# USB_JTAG.net
KiCad netlist of a schematic drawn in Altium Designer
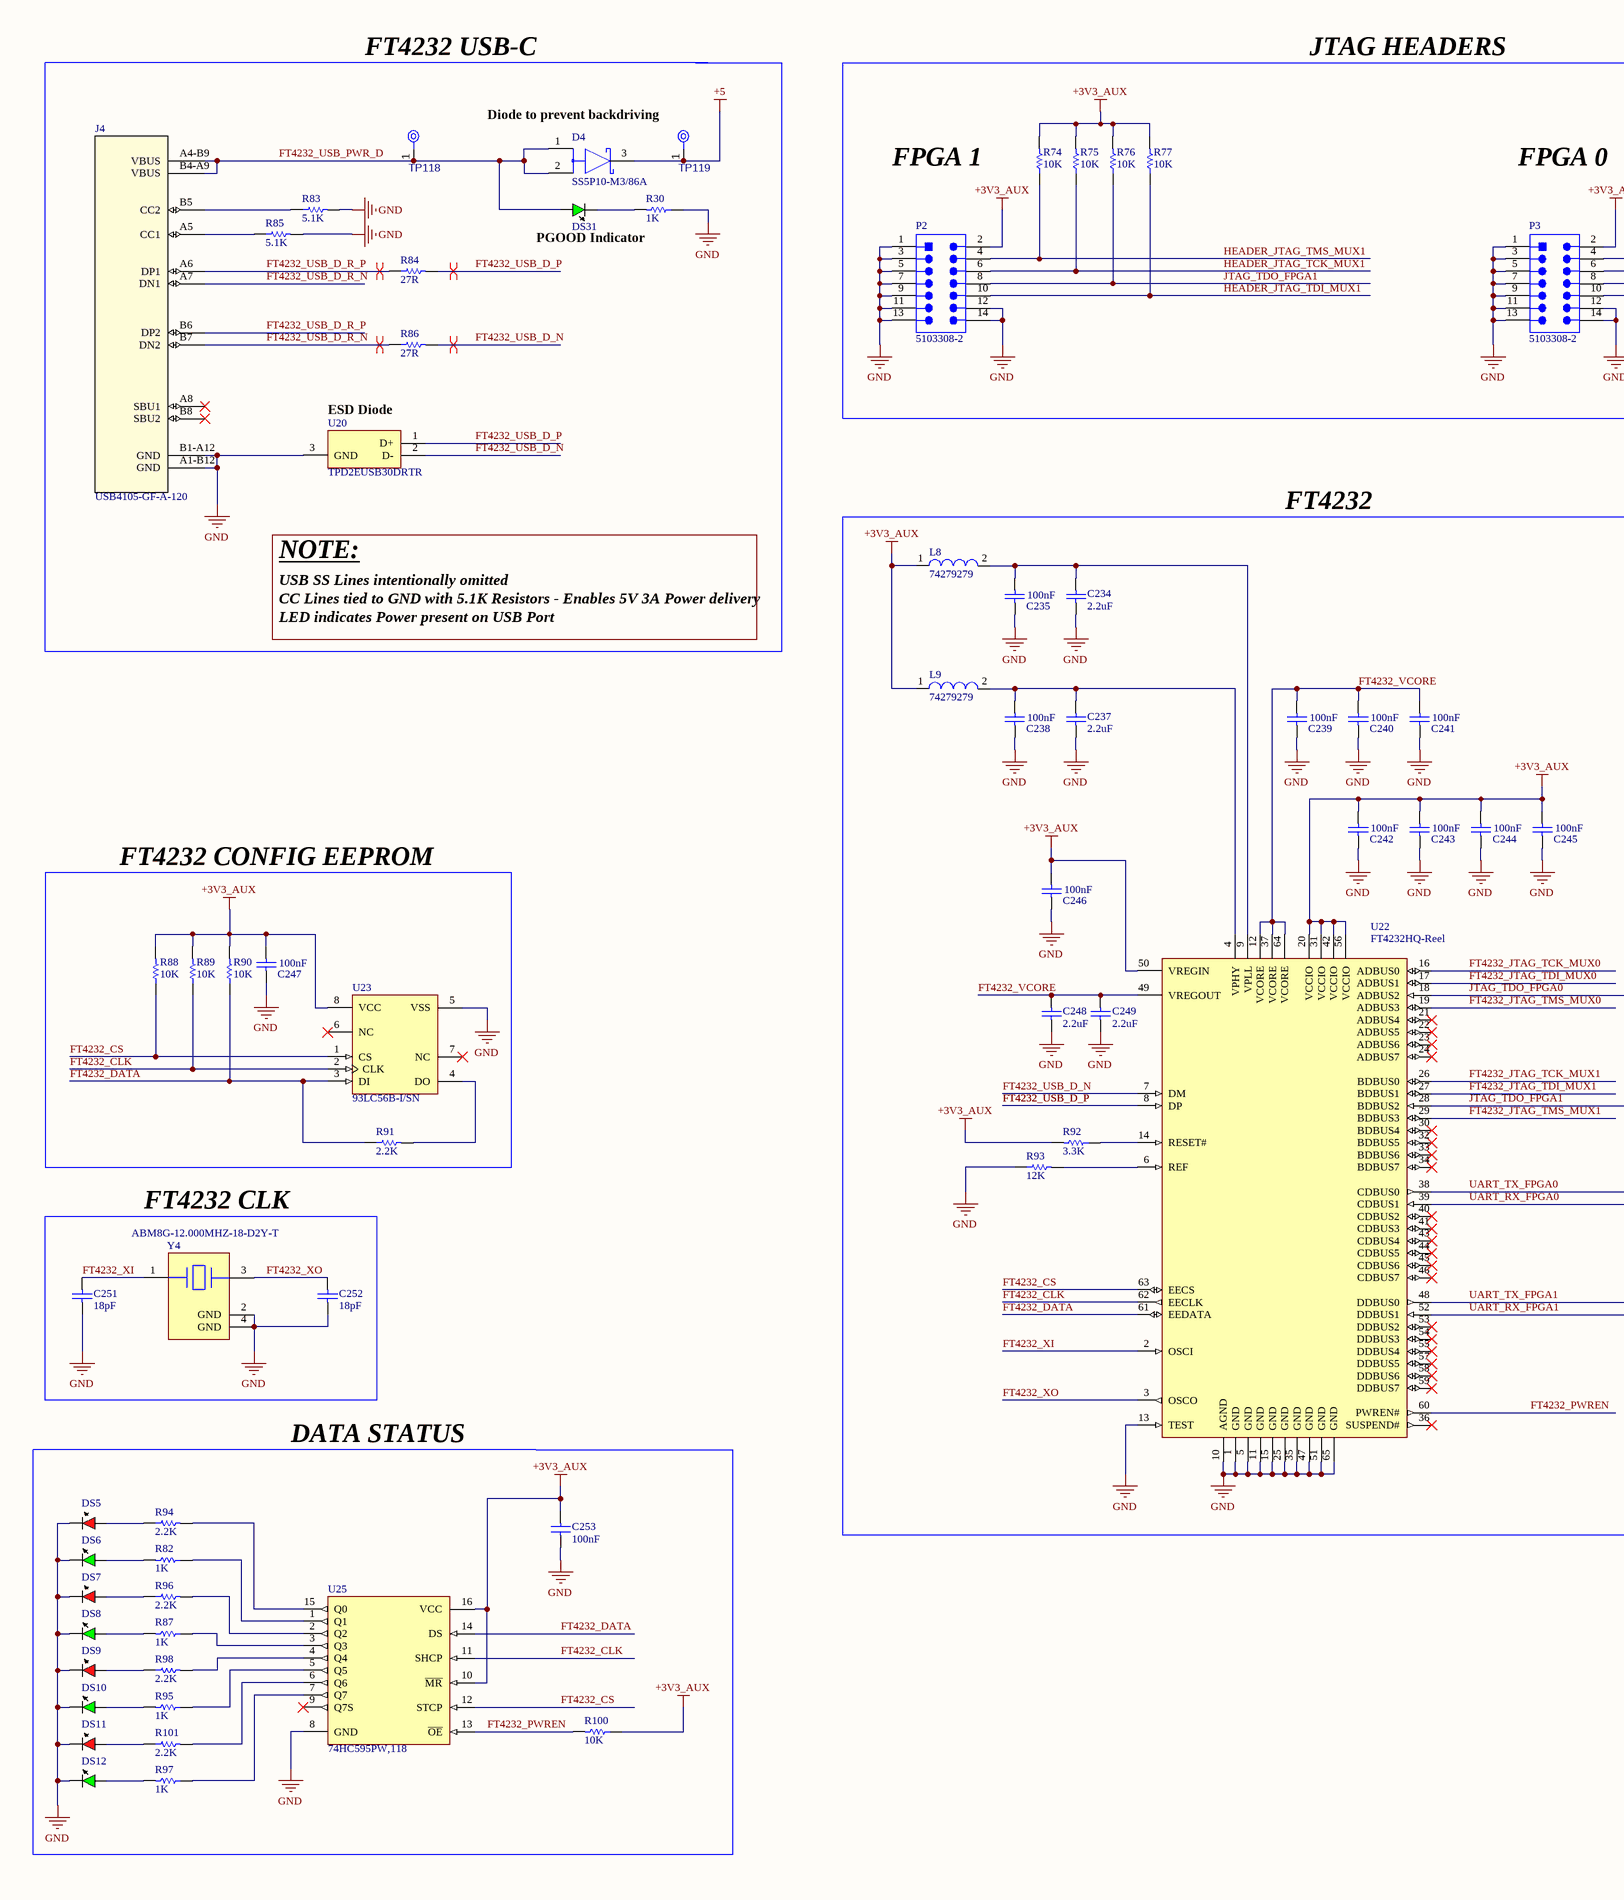
[diagram p0: USB JTAG.SchDoc, left]
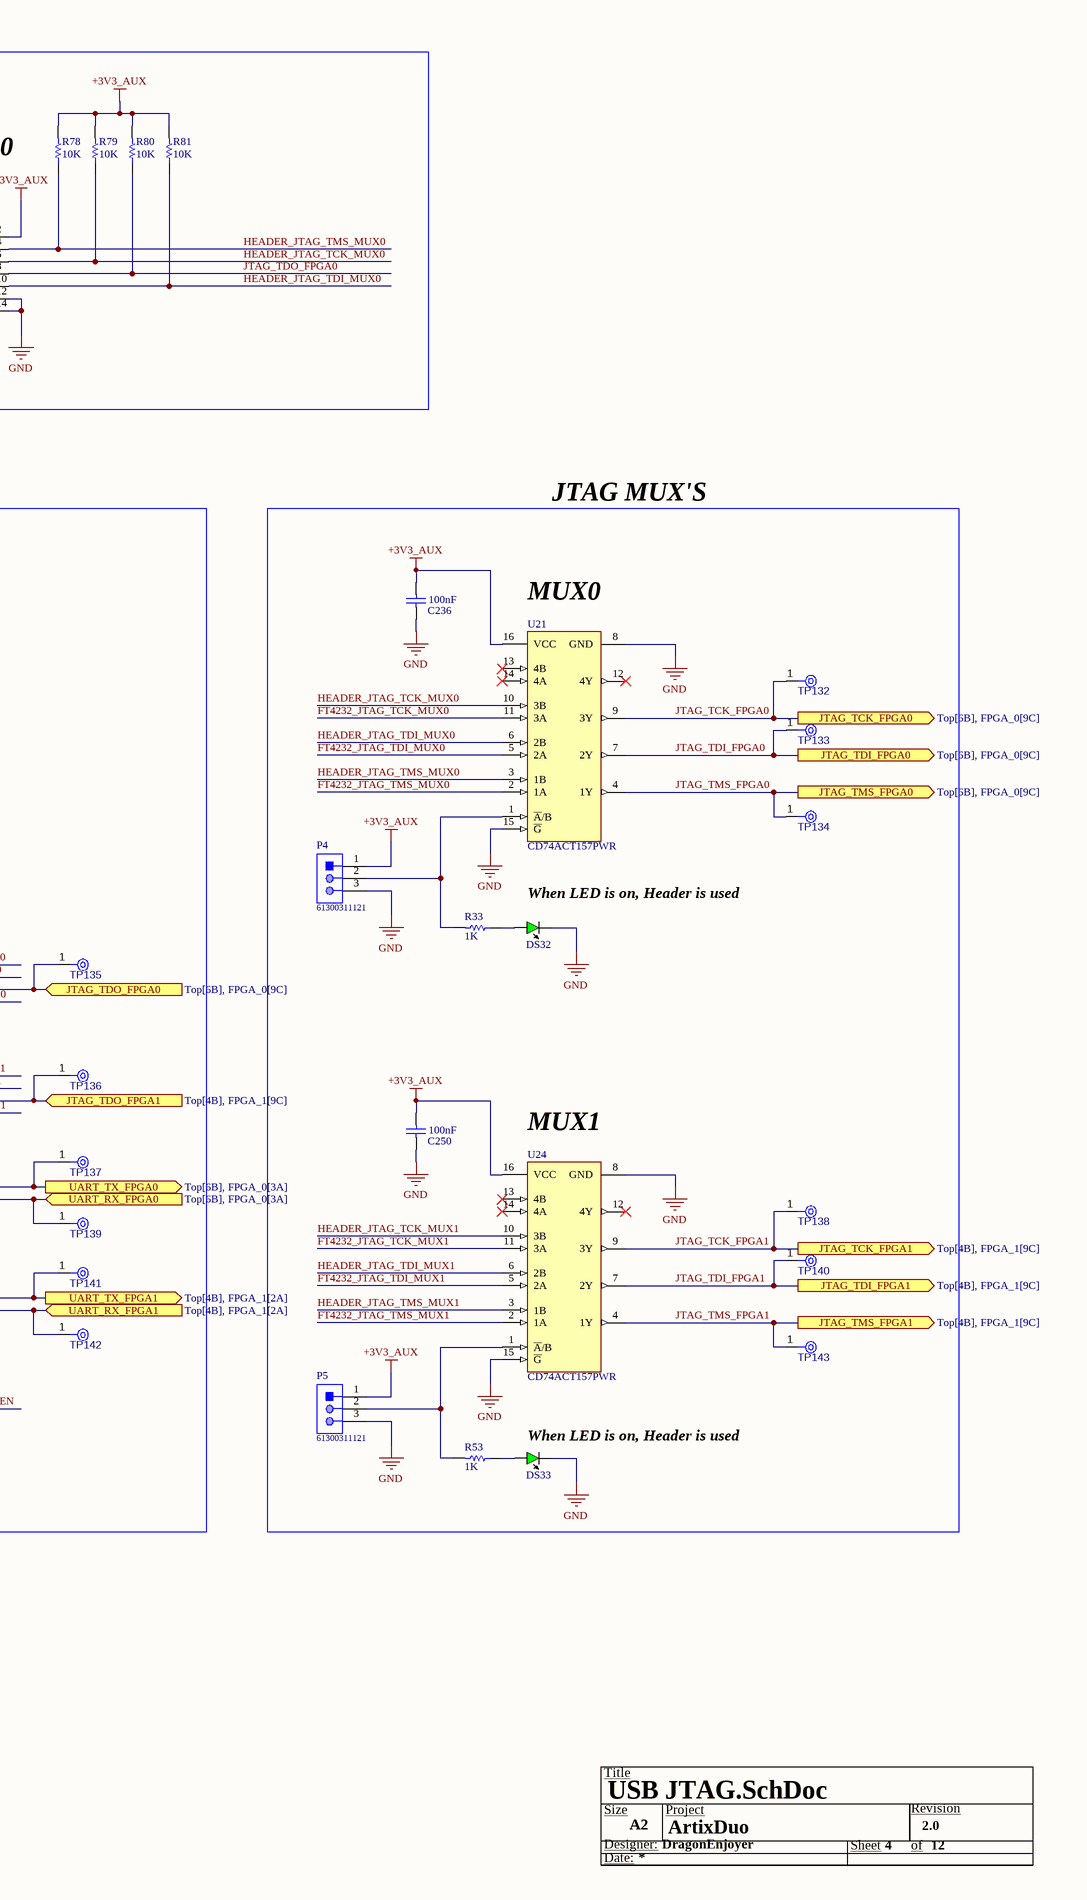
[diagram p1: USB JTAG.SchDoc, right]

(export (version "E")
  (design (tool "Eeschema 10.0.6"))
  (components
    (comp (ref "C234")
      (value "2.2uF")
      (footprint "CAPC1005X55X25NL05T10")
      (description "GRM155R60J225ME15D")
      (fields (field (name "MANUFACTURER") "Murata"))
      (libsource (lib "Altium Content Vault") (part "CAP"))
    )
    (comp (ref "C235")
      (value "100nF")
      (footprint "CAPC1005X05N")
      (description "Cap Ceramic 0.1uF 50V X7R 20% SMD 0402 125°C Paper T/R GRM155R71H104ME14J")
      (fields (field (name "VOLTAGE") "50V"))
      (libsource (lib "Main Workspace") (part "CAP"))
    )
    (comp (ref "C236")
      (value "100nF")
      (footprint "CAPC1005X05N")
      (description "Cap Ceramic 0.1uF 50V X7R 20% SMD 0402 125°C Paper T/R GRM155R71H104ME14J")
      (fields (field (name "VOLTAGE") "50V"))
      (libsource (lib "Main Workspace") (part "CAP"))
    )
    (comp (ref "C237")
      (value "2.2uF")
      (footprint "CAPC1005X55X25NL05T10")
      (description "GRM155R60J225ME15D")
      (fields (field (name "MANUFACTURER") "Murata"))
      (libsource (lib "Altium Content Vault") (part "CAP"))
    )
    (comp (ref "C238")
      (value "100nF")
      (footprint "CAPC1005X05N")
      (description "Cap Ceramic 0.1uF 50V X7R 20% SMD 0402 125°C Paper T/R GRM155R71H104ME14J")
      (fields (field (name "VOLTAGE") "50V"))
      (libsource (lib "Main Workspace") (part "CAP"))
    )
    (comp (ref "C239")
      (value "100nF")
      (footprint "CAPC1005X05N")
      (description "Cap Ceramic 0.1uF 50V X7R 20% SMD 0402 125°C Paper T/R GRM155R71H104ME14J")
      (fields (field (name "VOLTAGE") "50V"))
      (libsource (lib "Main Workspace") (part "CAP"))
    )
    (comp (ref "C240")
      (value "100nF")
      (footprint "CAPC1005X05N")
      (description "Cap Ceramic 0.1uF 50V X7R 20% SMD 0402 125°C Paper T/R GRM155R71H104ME14J")
      (fields (field (name "VOLTAGE") "50V"))
      (libsource (lib "Main Workspace") (part "CAP"))
    )
    (comp (ref "C241")
      (value "100nF")
      (footprint "CAPC1005X05N")
      (description "Cap Ceramic 0.1uF 50V X7R 20% SMD 0402 125°C Paper T/R GRM155R71H104ME14J")
      (fields (field (name "VOLTAGE") "50V"))
      (libsource (lib "Main Workspace") (part "CAP"))
    )
    (comp (ref "C242")
      (value "100nF")
      (footprint "CAPC1005X05N")
      (description "Cap Ceramic 0.1uF 50V X7R 20% SMD 0402 125°C Paper T/R GRM155R71H104ME14J")
      (fields (field (name "VOLTAGE") "50V"))
      (libsource (lib "Main Workspace") (part "CAP"))
    )
    (comp (ref "C243")
      (value "100nF")
      (footprint "CAPC1005X05N")
      (description "Cap Ceramic 0.1uF 50V X7R 20% SMD 0402 125°C Paper T/R GRM155R71H104ME14J")
      (fields (field (name "VOLTAGE") "50V"))
      (libsource (lib "Main Workspace") (part "CAP"))
    )
    (comp (ref "C244")
      (value "100nF")
      (footprint "CAPC1005X05N")
      (description "Cap Ceramic 0.1uF 50V X7R 20% SMD 0402 125°C Paper T/R GRM155R71H104ME14J")
      (fields (field (name "VOLTAGE") "50V"))
      (libsource (lib "Main Workspace") (part "CAP"))
    )
    (comp (ref "C245")
      (value "100nF")
      (footprint "CAPC1005X05N")
      (description "Cap Ceramic 0.1uF 50V X7R 20% SMD 0402 125°C Paper T/R GRM155R71H104ME14J")
      (fields (field (name "VOLTAGE") "50V"))
      (libsource (lib "Main Workspace") (part "CAP"))
    )
    (comp (ref "C246")
      (value "100nF")
      (footprint "CAPC1005X05N")
      (description "Cap Ceramic 0.1uF 50V X7R 20% SMD 0402 125°C Paper T/R GRM155R71H104ME14J")
      (fields (field (name "VOLTAGE") "50V"))
      (libsource (lib "Main Workspace") (part "CAP"))
    )
    (comp (ref "C247")
      (value "100nF")
      (footprint "CAPC1005X05N")
      (description "Cap Ceramic 0.1uF 50V X7R 20% SMD 0402 125°C Paper T/R GRM155R71H104ME14J")
      (fields (field (name "VOLTAGE") "50V"))
      (libsource (lib "Main Workspace") (part "CAP"))
    )
    (comp (ref "C248")
      (value "2.2uF")
      (footprint "CAPC1005X55X25NL05T10")
      (description "GRM155R60J225ME15D")
      (fields (field (name "MANUFACTURER") "Murata"))
      (libsource (lib "Altium Content Vault") (part "CAP"))
    )
    (comp (ref "C249")
      (value "2.2uF")
      (footprint "CAPC1005X55X25NL05T10")
      (description "GRM155R60J225ME15D")
      (fields (field (name "MANUFACTURER") "Murata"))
      (libsource (lib "Altium Content Vault") (part "CAP"))
    )
    (comp (ref "C250")
      (value "100nF")
      (footprint "CAPC1005X05N")
      (description "Cap Ceramic 0.1uF 50V X7R 20% SMD 0402 125°C Paper T/R GRM155R71H104ME14J")
      (fields (field (name "VOLTAGE") "50V"))
      (libsource (lib "Main Workspace") (part "CAP"))
    )
    (comp (ref "C251")
      (value "18pF")
      (footprint "CAPC1005X55X25LL05T10")
      (fields (field (name "MANUFACTURER") "Murata") (field (name "TOLERANCE") "±5%"))
      (libsource (lib "Altium Content Vault") (part "CAP-NP-2"))
    )
    (comp (ref "C252")
      (value "18pF")
      (footprint "CAPC1005X55X25LL05T10")
      (fields (field (name "MANUFACTURER") "Murata") (field (name "TOLERANCE") "±5%"))
      (libsource (lib "Altium Content Vault") (part "CAP-NP-2"))
    )
    (comp (ref "C253")
      (value "100nF")
      (footprint "CAPC1005X05N")
      (description "Cap Ceramic 0.1uF 50V X7R 20% SMD 0402 125°C Paper T/R GRM155R71H104ME14J")
      (fields (field (name "VOLTAGE") "50V"))
      (libsource (lib "Main Workspace") (part "CAP"))
    )
    (comp (ref "D4")
      (value "SS5P10-M3/86A")
      (footprint "FP-95570-MFG")
      (description "DIODE SCHOTTKY 100V 5A TO277A")
      (libsource (lib "Altium Content Vault") (part "03725f8997c85b601c823eea96032f8"))
    )
    (comp (ref "DS5")
      (value "TLMS1100-GS08")
      (footprint "VISH-TLMX1100_V")
      (description "LED Uni-Color Red 633nm Automotive 2-Pin Chip 0603(1608Metric) T/R")
      (libsource (lib "Main Workspace") (part "LED-RED-AK-2"))
    )
    (comp (ref "DS6")
      (value "SMLLX0603GWTR")
      (footprint "LUMX-SML-LX0603_V")
      (description "LED GREEN DIFFUSED SMD")
      (libsource (lib "Main Workspace") (part "LED-GREEN-AK-2"))
    )
    (comp (ref "DS7")
      (value "TLMS1100-GS08")
      (footprint "VISH-TLMX1100_V")
      (description "LED Uni-Color Red 633nm Automotive 2-Pin Chip 0603(1608Metric) T/R")
      (libsource (lib "Main Workspace") (part "LED-RED-AK-2"))
    )
    (comp (ref "DS8")
      (value "SMLLX0603GWTR")
      (footprint "LUMX-SML-LX0603_V")
      (description "LED GREEN DIFFUSED SMD")
      (libsource (lib "Main Workspace") (part "LED-GREEN-AK-2"))
    )
    (comp (ref "DS9")
      (value "TLMS1100-GS08")
      (footprint "VISH-TLMX1100_V")
      (description "LED Uni-Color Red 633nm Automotive 2-Pin Chip 0603(1608Metric) T/R")
      (libsource (lib "Main Workspace") (part "LED-RED-AK-2"))
    )
    (comp (ref "DS10")
      (value "SMLLX0603GWTR")
      (footprint "LUMX-SML-LX0603_V")
      (description "LED GREEN DIFFUSED SMD")
      (libsource (lib "Main Workspace") (part "LED-GREEN-AK-2"))
    )
    (comp (ref "DS11")
      (value "TLMS1100-GS08")
      (footprint "VISH-TLMX1100_V")
      (description "LED Uni-Color Red 633nm Automotive 2-Pin Chip 0603(1608Metric) T/R")
      (libsource (lib "Main Workspace") (part "LED-RED-AK-2"))
    )
    (comp (ref "DS12")
      (value "SMLLX0603GWTR")
      (footprint "LUMX-SML-LX0603_V")
      (description "LED GREEN DIFFUSED SMD")
      (libsource (lib "Main Workspace") (part "LED-GREEN-AK-2"))
    )
    (comp (ref "DS31")
      (value "SMLLX0603GWTR")
      (footprint "LUMX-SML-LX0603_V")
      (description "LED GREEN DIFFUSED SMD")
      (libsource (lib "Main Workspace") (part "LED-GREEN-AK-2"))
    )
    (comp (ref "DS32")
      (value "SMLLX0603GWTR")
      (footprint "LUMX-SML-LX0603_V")
      (description "LED GREEN DIFFUSED SMD")
      (libsource (lib "Main Workspace") (part "LED-GREEN-AK-2"))
    )
    (comp (ref "DS33")
      (value "SMLLX0603GWTR")
      (footprint "LUMX-SML-LX0603_V")
      (description "LED GREEN DIFFUSED SMD")
      (libsource (lib "Main Workspace") (part "LED-GREEN-AK-2"))
    )
    (comp (ref "J4")
      (value "USB4105-GF-A-120")
      (footprint "USB4105-GF-A-120-Footprint-1")
      (libsource (lib "Main Workspace") (part "USB4105-GF-A-120"))
    )
    (comp (ref "L8")
      (value "74279279")
      (footprint "SMD-0402")
      (description "SMD EMI Suppression Ferrite Bead WE-CBF, Z = 600 Ohm")
      (libsource (lib "Altium Content Vault") (part "PAS-IND-INDUCTOR-2"))
    )
    (comp (ref "L9")
      (value "74279279")
      (footprint "SMD-0402")
      (description "SMD EMI Suppression Ferrite Bead WE-CBF, Z = 600 Ohm")
      (libsource (lib "Altium Content Vault") (part "PAS-IND-INDUCTOR-2"))
    )
    (comp (ref "P2")
      (value "5103308-2")
      (footprint "TECO-5103308-2_V")
      (fields (field (name "MANUFACTURER") "TE Connectivity"))
      (libsource (lib "Altium Content Vault") (part "CN-2P-M-R14"))
    )
    (comp (ref "P3")
      (value "5103308-2")
      (footprint "TECO-5103308-2_V")
      (fields (field (name "MANUFACTURER") "TE Connectivity"))
      (libsource (lib "Altium Content Vault") (part "CN-2P-M-R14"))
    )
    (comp (ref "P4")
      (value "61300311121")
      (footprint "61300311121")
      (description "THT Vertical Pin Header WR-PHD, Pitch 2.54 mm, Single Row, 3 pins")
      (fields (field (name "MANUFACTURER") "Wurth Elektronik") (field (name "PUBLISHER") "WurthElektronik"))
      (libsource (lib "Altium Content Vault") (part "WE-CN-1P-M-R3"))
    )
    (comp (ref "P5")
      (value "61300311121")
      (footprint "61300311121")
      (description "THT Vertical Pin Header WR-PHD, Pitch 2.54 mm, Single Row, 3 pins")
      (fields (field (name "MANUFACTURER") "Wurth Elektronik") (field (name "PUBLISHER") "WurthElektronik"))
      (libsource (lib "Altium Content Vault") (part "WE-CN-1P-M-R3"))
    )
    (comp (ref "R30")
      (value "1K")
      (footprint "RESC1005X40X25NL05T10")
      (description "CRCW04021K00FKEDHP")
      (fields (field (name "MANUFACTURER") "Vishay Dale"))
      (libsource (lib "Altium Content Vault") (part "RES"))
    )
    (comp (ref "R33")
      (value "1K")
      (footprint "RESC1005X40X25NL05T10")
      (description "CRCW04021K00FKEDHP")
      (fields (field (name "MANUFACTURER") "Vishay Dale"))
      (libsource (lib "Altium Content Vault") (part "RES"))
    )
    (comp (ref "R53")
      (value "1K")
      (footprint "RESC1005X40X25NL05T10")
      (description "CRCW04021K00FKEDHP")
      (fields (field (name "MANUFACTURER") "Vishay Dale"))
      (libsource (lib "Altium Content Vault") (part "RES"))
    )
    (comp (ref "R74")
      (value "10K")
      (footprint "RESC1005X40X25NL05T10")
      (description "RC0402FR-0710KL")
      (fields (field (name "MANUFACTURER") "Yageo / Phycomp"))
      (libsource (lib "Altium Content Vault") (part "RES"))
    )
    (comp (ref "R75")
      (value "10K")
      (footprint "RESC1005X40X25NL05T10")
      (description "RC0402FR-0710KL")
      (fields (field (name "MANUFACTURER") "Yageo / Phycomp"))
      (libsource (lib "Altium Content Vault") (part "RES"))
    )
    (comp (ref "R76")
      (value "10K")
      (footprint "RESC1005X40X25NL05T10")
      (description "RC0402FR-0710KL")
      (fields (field (name "MANUFACTURER") "Yageo / Phycomp"))
      (libsource (lib "Altium Content Vault") (part "RES"))
    )
    (comp (ref "R77")
      (value "10K")
      (footprint "RESC1005X40X25NL05T10")
      (description "RC0402FR-0710KL")
      (fields (field (name "MANUFACTURER") "Yageo / Phycomp"))
      (libsource (lib "Altium Content Vault") (part "RES"))
    )
    (comp (ref "R78")
      (value "10K")
      (footprint "RESC1005X40X25NL05T10")
      (description "RC0402FR-0710KL")
      (fields (field (name "MANUFACTURER") "Yageo / Phycomp"))
      (libsource (lib "Altium Content Vault") (part "RES"))
    )
    (comp (ref "R79")
      (value "10K")
      (footprint "RESC1005X40X25NL05T10")
      (description "RC0402FR-0710KL")
      (fields (field (name "MANUFACTURER") "Yageo / Phycomp"))
      (libsource (lib "Altium Content Vault") (part "RES"))
    )
    (comp (ref "R80")
      (value "10K")
      (footprint "RESC1005X40X25NL05T10")
      (description "RC0402FR-0710KL")
      (fields (field (name "MANUFACTURER") "Yageo / Phycomp"))
      (libsource (lib "Altium Content Vault") (part "RES"))
    )
    (comp (ref "R81")
      (value "10K")
      (footprint "RESC1005X40X25NL05T10")
      (description "RC0402FR-0710KL")
      (fields (field (name "MANUFACTURER") "Yageo / Phycomp"))
      (libsource (lib "Altium Content Vault") (part "RES"))
    )
    (comp (ref "R82")
      (value "1K")
      (footprint "RESC1005X40X25NL05T10")
      (description "CRCW04021K00FKEDHP")
      (fields (field (name "MANUFACTURER") "Vishay Dale"))
      (libsource (lib "Altium Content Vault") (part "RES"))
    )
    (comp (ref "R83")
      (value "5.1K")
      (footprint "RESC1005X40X25NL05T10")
      (description "RC0402FR-075K1L")
      (fields (field (name "MANUFACTURER") "Yageo / Phycomp"))
      (libsource (lib "Altium Content Vault") (part "RES"))
    )
    (comp (ref "R84")
      (value "27R")
      (footprint "RESC1005X40X25NL05T10")
      (description "RC0402JR-0727RL")
      (fields (field (name "MANUFACTURER") "Yageo / Phycomp"))
      (libsource (lib "Altium Content Vault") (part "RES"))
    )
    (comp (ref "R85")
      (value "5.1K")
      (footprint "RESC1005X40X25NL05T10")
      (description "RC0402FR-075K1L")
      (fields (field (name "MANUFACTURER") "Yageo / Phycomp"))
      (libsource (lib "Altium Content Vault") (part "RES"))
    )
    (comp (ref "R86")
      (value "27R")
      (footprint "RESC1005X40X25NL05T10")
      (description "RC0402JR-0727RL")
      (fields (field (name "MANUFACTURER") "Yageo / Phycomp"))
      (libsource (lib "Altium Content Vault") (part "RES"))
    )
    (comp (ref "R87")
      (value "1K")
      (footprint "RESC1005X40X25NL05T10")
      (description "CRCW04021K00FKEDHP")
      (fields (field (name "MANUFACTURER") "Vishay Dale"))
      (libsource (lib "Altium Content Vault") (part "RES"))
    )
    (comp (ref "R88")
      (value "10K")
      (footprint "RESC1005X40X25NL05T10")
      (description "RC0402FR-0710KL")
      (fields (field (name "MANUFACTURER") "Yageo / Phycomp"))
      (libsource (lib "Altium Content Vault") (part "RES"))
    )
    (comp (ref "R89")
      (value "10K")
      (footprint "RESC1005X40X25NL05T10")
      (description "RC0402FR-0710KL")
      (fields (field (name "MANUFACTURER") "Yageo / Phycomp"))
      (libsource (lib "Altium Content Vault") (part "RES"))
    )
    (comp (ref "R90")
      (value "10K")
      (footprint "RESC1005X40X25NL05T10")
      (description "RC0402FR-0710KL")
      (fields (field (name "MANUFACTURER") "Yageo / Phycomp"))
      (libsource (lib "Altium Content Vault") (part "RES"))
    )
    (comp (ref "R91")
      (value "2.2K")
      (footprint "RESC1005X40X25NL5T10")
      (fields (field (name "TOLERANCE") "5%"))
      (libsource (lib "Altium Content Vault") (part "RES-2"))
    )
    (comp (ref "R92")
      (value "3.3K")
      (footprint "RESC1005X40X25NL05T10")
      (description "CRCW04023K30FKEDHP")
      (fields (field (name "MANUFACTURER") "Vishay Dale"))
      (libsource (lib "Altium Content Vault") (part "RES"))
    )
    (comp (ref "R93")
      (value "12K")
      (footprint "RESC1005X40X25NL05T05")
      (description "CRCW040212K0FKED")
      (fields (field (name "MANUFACTURER") "Vishay Dale"))
      (libsource (lib "Altium Content Vault") (part "RES"))
    )
    (comp (ref "R94")
      (value "2.2K")
      (footprint "RESC1005X40X25NL5T10")
      (fields (field (name "TOLERANCE") "5%"))
      (libsource (lib "Altium Content Vault") (part "RES-2"))
    )
    (comp (ref "R95")
      (value "1K")
      (footprint "RESC1005X40X25NL05T10")
      (description "CRCW04021K00FKEDHP")
      (fields (field (name "MANUFACTURER") "Vishay Dale"))
      (libsource (lib "Altium Content Vault") (part "RES"))
    )
    (comp (ref "R96")
      (value "2.2K")
      (footprint "RESC1005X40X25NL5T10")
      (fields (field (name "TOLERANCE") "5%"))
      (libsource (lib "Altium Content Vault") (part "RES-2"))
    )
    (comp (ref "R97")
      (value "1K")
      (footprint "RESC1005X40X25NL05T10")
      (description "CRCW04021K00FKEDHP")
      (fields (field (name "MANUFACTURER") "Vishay Dale"))
      (libsource (lib "Altium Content Vault") (part "RES"))
    )
    (comp (ref "R98")
      (value "2.2K")
      (footprint "RESC1005X40X25NL5T10")
      (fields (field (name "TOLERANCE") "5%"))
      (libsource (lib "Altium Content Vault") (part "RES-2"))
    )
    (comp (ref "R100")
      (value "10K")
      (footprint "RESC1005X40X25NL05T10")
      (description "RC0402FR-0710KL")
      (fields (field (name "MANUFACTURER") "Yageo / Phycomp"))
      (libsource (lib "Altium Content Vault") (part "RES"))
    )
    (comp (ref "R101")
      (value "2.2K")
      (footprint "RESC1005X40X25NL5T10")
      (fields (field (name "TOLERANCE") "5%"))
      (libsource (lib "Altium Content Vault") (part "RES-2"))
    )
    (comp (ref "TP118")
      (value "TPAD6R")
      (footprint "TP06R")
      (description "0.6mm round")
      (libsource (lib "Main Workspace") (part "CMP-001-0001-4"))
    )
    (comp (ref "TP119")
      (value "TPAD6R")
      (footprint "TP06R")
      (description "0.6mm round")
      (libsource (lib "Main Workspace") (part "CMP-001-0001-4"))
    )
    (comp (ref "TP132")
      (value "TPAD6R")
      (footprint "TP06R")
      (description "0.6mm round")
      (libsource (lib "Main Workspace") (part "CMP-001-0001-4"))
    )
    (comp (ref "TP133")
      (value "TPAD6R")
      (footprint "TP06R")
      (description "0.6mm round")
      (libsource (lib "Main Workspace") (part "CMP-001-0001-4"))
    )
    (comp (ref "TP134")
      (value "TPAD6R")
      (footprint "TP06R")
      (description "0.6mm round")
      (libsource (lib "Main Workspace") (part "CMP-001-0001-4"))
    )
    (comp (ref "TP135")
      (value "TPAD6R")
      (footprint "TP06R")
      (description "0.6mm round")
      (libsource (lib "Main Workspace") (part "CMP-001-0001-4"))
    )
    (comp (ref "TP136")
      (value "TPAD6R")
      (footprint "TP06R")
      (description "0.6mm round")
      (libsource (lib "Main Workspace") (part "CMP-001-0001-4"))
    )
    (comp (ref "TP137")
      (value "TPAD6R")
      (footprint "TP06R")
      (description "0.6mm round")
      (libsource (lib "Main Workspace") (part "CMP-001-0001-4"))
    )
    (comp (ref "TP138")
      (value "TPAD6R")
      (footprint "TP06R")
      (description "0.6mm round")
      (libsource (lib "Main Workspace") (part "CMP-001-0001-4"))
    )
    (comp (ref "TP139")
      (value "TPAD6R")
      (footprint "TP06R")
      (description "0.6mm round")
      (libsource (lib "Main Workspace") (part "CMP-001-0001-4"))
    )
    (comp (ref "TP140")
      (value "TPAD6R")
      (footprint "TP06R")
      (description "0.6mm round")
      (libsource (lib "Main Workspace") (part "CMP-001-0001-4"))
    )
    (comp (ref "TP141")
      (value "TPAD6R")
      (footprint "TP06R")
      (description "0.6mm round")
      (libsource (lib "Main Workspace") (part "CMP-001-0001-4"))
    )
    (comp (ref "TP142")
      (value "TPAD6R")
      (footprint "TP06R")
      (description "0.6mm round")
      (libsource (lib "Main Workspace") (part "CMP-001-0001-4"))
    )
    (comp (ref "TP143")
      (value "TPAD6R")
      (footprint "TP06R")
      (description "0.6mm round")
      (libsource (lib "Main Workspace") (part "CMP-001-0001-4"))
    )
    (comp (ref "U20")
      (value "TPD2EUSB30DRTR")
      (footprint "DRT0003A")
      (fields (field (name "MANUFACTURER") "Texas Instruments"))
      (libsource (lib "Altium Content Vault") (part "TI-TPD2EUSB30-SOT_DRT-3"))
    )
    (comp (ref "U21")
      (value "CD74ACT157PWR")
      (footprint "PW0016A_L")
      (description "Quad Non-Inverting 2-Input Multiplexers, PW0016A, LARGE T&R")
      (fields
        (field (name "MANUFACTURER") "Texas Instruments")
        (field (name "GENERIC PART NUMBER") "CD74ACT157")
      )
      (libsource (lib "Altium Content Vault") (part "TI-XXX4XXXX15XX-16"))
    )
    (comp (ref "U22")
      (value "FT4232HQ-Reel")
      (footprint "QFN64_2_M")
      (description "Quad High Speed USB To Multipurpose UART/MPSSE IC, 64-pin QFN, Tape and Reel")
      (fields (field (name "MANUFACTURER") "FTDI"))
      (libsource (lib "Altium Content Vault") (part "COM-UART-FT4232H-QFN64"))
    )
    (comp (ref "U23")
      (value "93LC56B-I/SN")
      (footprint "SOIC-SN8_L")
      (description "2K, 128x16-bit, 2.5V Microwire Serial EEPROM, 8-Pin SOIC 150mil, Industrial Temperature")
      (libsource (lib "Altium Content Vault") (part "MEM-SEEPROM-93AA46B-P-8"))
    )
    (comp (ref "U24")
      (value "CD74ACT157PWR")
      (footprint "PW0016A_L")
      (description "Quad Non-Inverting 2-Input Multiplexers, PW0016A, LARGE T&R")
      (fields
        (field (name "MANUFACTURER") "Texas Instruments")
        (field (name "GENERIC PART NUMBER") "CD74ACT157")
      )
      (libsource (lib "Altium Content Vault") (part "TI-XXX4XXXX15XX-16"))
    )
    (comp (ref "U25")
      (value "74HC595PW,118")
      (footprint "FP-SOT403-1-MFG")
      (description "IC SHIFT REGISTER 8BIT 16TSSOP")
      (libsource (lib "Altium Content Vault") (part "27683e23285b137cd268a0f18c66bed"))
    )
    (comp (ref "Y4")
      (value "ABM8G-12.000MHZ-18-D2Y-T")
      (footprint "FP-ABM8G-MFG")
      (description "Crystal 12MHz ±20ppm (Tol) ±30ppm (Stability) 18pF FUND 120Ω 4-Pin SMD T/R")
      (fields (field (name "TOLERANCE") "20ppm"))
      (libsource (lib "Altium Content Vault") (part "48e526d86b7f2615d98721063c72f49"))
    )
  )
  (nets
    (net (code "1") (name "+3V3_AUX") (class "Default")
      (node (ref "C236") (pin "2") (pinfunction "2_2") (pintype "passive"))
      (node (ref "C242") (pin "2") (pinfunction "2_2") (pintype "passive"))
      (node (ref "C243") (pin "2") (pinfunction "2_2") (pintype "passive"))
      (node (ref "C244") (pin "2") (pinfunction "2_2") (pintype "passive"))
      (node (ref "C245") (pin "2") (pinfunction "2_2") (pintype "passive"))
      (node (ref "C246") (pin "2") (pinfunction "2_2") (pintype "passive"))
      (node (ref "C247") (pin "2") (pinfunction "2_2") (pintype "passive"))
      (node (ref "C250") (pin "2") (pinfunction "2_2") (pintype "passive"))
      (node (ref "C253") (pin "2") (pinfunction "2_2") (pintype "passive"))
      (node (ref "L8") (pin "1") (pinfunction "1_1") (pintype "passive"))
      (node (ref "L9") (pin "1") (pinfunction "1_1") (pintype "passive"))
      (node (ref "P2") (pin "2") (pinfunction "2_2") (pintype "passive"))
      (node (ref "P3") (pin "2") (pinfunction "2_2") (pintype "passive"))
      (node (ref "P4") (pin "1") (pinfunction "1_1") (pintype "passive"))
      (node (ref "P5") (pin "1") (pinfunction "1_1") (pintype "passive"))
      (node (ref "R100") (pin "1") (pinfunction "1_1") (pintype "passive"))
      (node (ref "R74") (pin "2") (pinfunction "2_2") (pintype "passive"))
      (node (ref "R75") (pin "2") (pinfunction "2_2") (pintype "passive"))
      (node (ref "R76") (pin "2") (pinfunction "2_2") (pintype "passive"))
      (node (ref "R77") (pin "2") (pinfunction "2_2") (pintype "passive"))
      (node (ref "R78") (pin "2") (pinfunction "2_2") (pintype "passive"))
      (node (ref "R79") (pin "2") (pinfunction "2_2") (pintype "passive"))
      (node (ref "R80") (pin "2") (pinfunction "2_2") (pintype "passive"))
      (node (ref "R81") (pin "2") (pinfunction "2_2") (pintype "passive"))
      (node (ref "R88") (pin "2") (pinfunction "2_2") (pintype "passive"))
      (node (ref "R89") (pin "2") (pinfunction "2_2") (pintype "passive"))
      (node (ref "R90") (pin "2") (pinfunction "2_2") (pintype "passive"))
      (node (ref "R92") (pin "2") (pinfunction "2_2") (pintype "passive"))
      (node (ref "U21") (pin "16") (pinfunction "VCC_16") (pintype "power_in"))
      (node (ref "U22") (pin "20") (pinfunction "VCCIO_20") (pintype "power_in"))
      (node (ref "U22") (pin "31") (pinfunction "VCCIO_31") (pintype "power_in"))
      (node (ref "U22") (pin "42") (pinfunction "VCCIO_42") (pintype "power_in"))
      (node (ref "U22") (pin "50") (pinfunction "VREGIN_50") (pintype "power_in"))
      (node (ref "U22") (pin "56") (pinfunction "VCCIO_56") (pintype "power_in"))
      (node (ref "U23") (pin "8") (pinfunction "VCC_8") (pintype "power_in"))
      (node (ref "U24") (pin "16") (pinfunction "VCC_16") (pintype "power_in"))
      (node (ref "U25") (pin "10") (pinfunction "~{MR}_10") (pintype "input"))
      (node (ref "U25") (pin "16") (pinfunction "VCC_16") (pintype "power_in"))
    )
    (net (code "2") (name "+5") (class "Default")
      (node (ref "D4") (pin "3") (pinfunction "C_3") (pintype "passive"))
      (node (ref "TP119") (pin "1") (pinfunction "TP_1") (pintype "passive"))
    )
    (net (code "3") (name "/FT4232_CLK") (class "Default")
      (node (ref "R89") (pin "1") (pinfunction "1_1") (pintype "passive"))
      (node (ref "U22") (pin "62") (pinfunction "EECLK_62") (pintype "output"))
      (node (ref "U23") (pin "2") (pinfunction "CLK_2") (pintype "input"))
      (node (ref "U25") (pin "11") (pinfunction "SHCP_11") (pintype "input"))
    )
    (net (code "4") (name "/FT4232_CS") (class "Default")
      (node (ref "R88") (pin "1") (pinfunction "1_1") (pintype "passive"))
      (node (ref "U22") (pin "63") (pinfunction "EECS_63") (pintype "bidirectional"))
      (node (ref "U23") (pin "1") (pinfunction "CS_1") (pintype "input"))
      (node (ref "U25") (pin "12") (pinfunction "STCP_12") (pintype "input"))
    )
    (net (code "5") (name "/FT4232_DATA") (class "Default")
      (node (ref "R90") (pin "1") (pinfunction "1_1") (pintype "passive"))
      (node (ref "R91") (pin "1") (pinfunction "1_1") (pintype "passive"))
      (node (ref "U22") (pin "61") (pinfunction "EEDATA_61") (pintype "bidirectional"))
      (node (ref "U23") (pin "3") (pinfunction "DI_3") (pintype "input"))
      (node (ref "U25") (pin "14") (pinfunction "DS_14") (pintype "input"))
    )
    (net (code "6") (name "/FT4232_JTAG_TCK_MUX0") (class "Default")
      (node (ref "U21") (pin "11") (pinfunction "3A_11") (pintype "input"))
      (node (ref "U22") (pin "16") (pinfunction "ADBUS0_16") (pintype "bidirectional"))
    )
    (net (code "7") (name "/FT4232_JTAG_TCK_MUX1") (class "Default")
      (node (ref "U22") (pin "26") (pinfunction "BDBUS0_26") (pintype "bidirectional"))
      (node (ref "U24") (pin "11") (pinfunction "3A_11") (pintype "input"))
    )
    (net (code "8") (name "/FT4232_JTAG_TDI_MUX0") (class "Default")
      (node (ref "U21") (pin "5") (pinfunction "2A_5") (pintype "input"))
      (node (ref "U22") (pin "17") (pinfunction "ADBUS1_17") (pintype "bidirectional"))
    )
    (net (code "9") (name "/FT4232_JTAG_TDI_MUX1") (class "Default")
      (node (ref "U22") (pin "27") (pinfunction "BDBUS1_27") (pintype "bidirectional"))
      (node (ref "U24") (pin "5") (pinfunction "2A_5") (pintype "input"))
    )
    (net (code "10") (name "/FT4232_JTAG_TMS_MUX0") (class "Default")
      (node (ref "U21") (pin "2") (pinfunction "1A_2") (pintype "input"))
      (node (ref "U22") (pin "19") (pinfunction "ADBUS3_19") (pintype "bidirectional"))
    )
    (net (code "11") (name "/FT4232_JTAG_TMS_MUX1") (class "Default")
      (node (ref "U22") (pin "29") (pinfunction "BDBUS3_29") (pintype "bidirectional"))
      (node (ref "U24") (pin "2") (pinfunction "1A_2") (pintype "input"))
    )
    (net (code "12") (name "/FT4232_PWREN") (class "Default")
      (node (ref "R100") (pin "2") (pinfunction "2_2") (pintype "passive"))
      (node (ref "U22") (pin "60") (pinfunction "PWREN#_60") (pintype "output"))
      (node (ref "U25") (pin "13") (pinfunction "~{OE}_13") (pintype "input"))
    )
    (net (code "13") (name "/FT4232_USB_D_N") (class "Default")
      (node (ref "R86") (pin "2") (pinfunction "2_2") (pintype "passive"))
      (node (ref "U20") (pin "2") (pinfunction "D-_2") (pintype "passive"))
      (node (ref "U22") (pin "7") (pinfunction "DM_7") (pintype "input"))
    )
    (net (code "14") (name "/FT4232_USB_D_P") (class "Default")
      (node (ref "R84") (pin "2") (pinfunction "2_2") (pintype "passive"))
      (node (ref "U20") (pin "1") (pinfunction "D+_1") (pintype "passive"))
      (node (ref "U22") (pin "8") (pinfunction "DP_8") (pintype "input"))
    )
    (net (code "15") (name "/FT4232_USB_D_R_N") (class "Default")
      (node (ref "J4") (pin "A7") (pinfunction "DN1_A7") (pintype "bidirectional"))
      (node (ref "J4") (pin "B7") (pinfunction "DN2_B7") (pintype "bidirectional"))
      (node (ref "R86") (pin "1") (pinfunction "1_1") (pintype "passive"))
    )
    (net (code "16") (name "/FT4232_USB_D_R_P") (class "Default")
      (node (ref "J4") (pin "A6") (pinfunction "DP1_A6") (pintype "bidirectional"))
      (node (ref "J4") (pin "B6") (pinfunction "DP2_B6") (pintype "bidirectional"))
      (node (ref "R84") (pin "1") (pinfunction "1_1") (pintype "passive"))
    )
    (net (code "17") (name "/FT4232_USB_PWR_D") (class "Default")
      (node (ref "D4") (pin "1") (pinfunction "A_1") (pintype "passive"))
      (node (ref "D4") (pin "2") (pinfunction "A_2") (pintype "passive"))
      (node (ref "DS31") (pin "1") (pinfunction "A_1") (pintype "passive"))
      (node (ref "J4") (pin "A4-B9") (pinfunction "VBUS_A4-B9") (pintype "power_in"))
      (node (ref "J4") (pin "B4-A9") (pinfunction "VBUS_B4-A9") (pintype "power_in"))
      (node (ref "TP118") (pin "1") (pinfunction "TP_1") (pintype "passive"))
    )
    (net (code "18") (name "/FT4232_VCORE") (class "Default")
      (node (ref "C239") (pin "2") (pinfunction "2_2") (pintype "passive"))
      (node (ref "C240") (pin "2") (pinfunction "2_2") (pintype "passive"))
      (node (ref "C241") (pin "2") (pinfunction "2_2") (pintype "passive"))
      (node (ref "C248") (pin "2") (pinfunction "2_2") (pintype "passive"))
      (node (ref "C249") (pin "2") (pinfunction "2_2") (pintype "passive"))
      (node (ref "U22") (pin "12") (pinfunction "VCORE_12") (pintype "power_in"))
      (node (ref "U22") (pin "37") (pinfunction "VCORE_37") (pintype "power_in"))
      (node (ref "U22") (pin "49") (pinfunction "VREGOUT_49") (pintype "power_in"))
      (node (ref "U22") (pin "64") (pinfunction "VCORE_64") (pintype "power_in"))
    )
    (net (code "19") (name "/FT4232_XI") (class "Default")
      (node (ref "C251") (pin "2") (pinfunction "2_2") (pintype "passive"))
      (node (ref "U22") (pin "2") (pinfunction "OSCI_2") (pintype "input"))
      (node (ref "Y4") (pin "1") (pinfunction "1_1") (pintype "passive"))
    )
    (net (code "20") (name "/FT4232_XO") (class "Default")
      (node (ref "C252") (pin "2") (pinfunction "2_2") (pintype "passive"))
      (node (ref "U22") (pin "3") (pinfunction "OSCO_3") (pintype "output"))
      (node (ref "Y4") (pin "3") (pinfunction "3_3") (pintype "passive"))
    )
    (net (code "21") (name "/HEADER_JTAG_TCK_MUX0") (class "Default")
      (node (ref "P3") (pin "6") (pinfunction "6_6") (pintype "passive"))
      (node (ref "R79") (pin "1") (pinfunction "1_1") (pintype "passive"))
      (node (ref "U21") (pin "10") (pinfunction "3B_10") (pintype "input"))
    )
    (net (code "22") (name "/HEADER_JTAG_TCK_MUX1") (class "Default")
      (node (ref "P2") (pin "6") (pinfunction "6_6") (pintype "passive"))
      (node (ref "R75") (pin "1") (pinfunction "1_1") (pintype "passive"))
      (node (ref "U24") (pin "10") (pinfunction "3B_10") (pintype "input"))
    )
    (net (code "23") (name "/HEADER_JTAG_TDI_MUX0") (class "Default")
      (node (ref "P3") (pin "10") (pinfunction "10_10") (pintype "passive"))
      (node (ref "R81") (pin "1") (pinfunction "1_1") (pintype "passive"))
      (node (ref "U21") (pin "6") (pinfunction "2B_6") (pintype "input"))
    )
    (net (code "24") (name "/HEADER_JTAG_TDI_MUX1") (class "Default")
      (node (ref "P2") (pin "10") (pinfunction "10_10") (pintype "passive"))
      (node (ref "R77") (pin "1") (pinfunction "1_1") (pintype "passive"))
      (node (ref "U24") (pin "6") (pinfunction "2B_6") (pintype "input"))
    )
    (net (code "25") (name "/HEADER_JTAG_TMS_MUX0") (class "Default")
      (node (ref "P3") (pin "4") (pinfunction "4_4") (pintype "passive"))
      (node (ref "R78") (pin "1") (pinfunction "1_1") (pintype "passive"))
      (node (ref "U21") (pin "3") (pinfunction "1B_3") (pintype "input"))
    )
    (net (code "26") (name "/HEADER_JTAG_TMS_MUX1") (class "Default")
      (node (ref "P2") (pin "4") (pinfunction "4_4") (pintype "passive"))
      (node (ref "R74") (pin "1") (pinfunction "1_1") (pintype "passive"))
      (node (ref "U24") (pin "3") (pinfunction "1B_3") (pintype "input"))
    )
    (net (code "27") (name "/JTAG_TCK_FPGA0") (class "Default")
      (node (ref "TP132") (pin "1") (pinfunction "TP_1") (pintype "passive"))
      (node (ref "U21") (pin "9") (pinfunction "3Y_9") (pintype "output"))
    )
    (net (code "28") (name "/JTAG_TCK_FPGA1") (class "Default")
      (node (ref "TP138") (pin "1") (pinfunction "TP_1") (pintype "passive"))
      (node (ref "U24") (pin "9") (pinfunction "3Y_9") (pintype "output"))
    )
    (net (code "29") (name "/JTAG_TDI_FPGA0") (class "Default")
      (node (ref "TP133") (pin "1") (pinfunction "TP_1") (pintype "passive"))
      (node (ref "U21") (pin "7") (pinfunction "2Y_7") (pintype "output"))
    )
    (net (code "30") (name "/JTAG_TDI_FPGA1") (class "Default")
      (node (ref "TP140") (pin "1") (pinfunction "TP_1") (pintype "passive"))
      (node (ref "U24") (pin "7") (pinfunction "2Y_7") (pintype "output"))
    )
    (net (code "31") (name "/JTAG_TDO_FPGA0") (class "Default")
      (node (ref "P3") (pin "8") (pinfunction "8_8") (pintype "passive"))
      (node (ref "R80") (pin "1") (pinfunction "1_1") (pintype "passive"))
      (node (ref "TP135") (pin "1") (pinfunction "TP_1") (pintype "passive"))
      (node (ref "U22") (pin "18") (pinfunction "ADBUS2_18") (pintype "input"))
    )
    (net (code "32") (name "/JTAG_TDO_FPGA1") (class "Default")
      (node (ref "P2") (pin "8") (pinfunction "8_8") (pintype "passive"))
      (node (ref "R76") (pin "1") (pinfunction "1_1") (pintype "passive"))
      (node (ref "TP136") (pin "1") (pinfunction "TP_1") (pintype "passive"))
      (node (ref "U22") (pin "28") (pinfunction "BDBUS2_28") (pintype "input"))
    )
    (net (code "33") (name "/JTAG_TMS_FPGA0") (class "Default")
      (node (ref "TP134") (pin "1") (pinfunction "TP_1") (pintype "passive"))
      (node (ref "U21") (pin "4") (pinfunction "1Y_4") (pintype "output"))
    )
    (net (code "34") (name "/JTAG_TMS_FPGA1") (class "Default")
      (node (ref "TP143") (pin "1") (pinfunction "TP_1") (pintype "passive"))
      (node (ref "U24") (pin "4") (pinfunction "1Y_4") (pintype "output"))
    )
    (net (code "35") (name "/UART_RX_FPGA0") (class "Default")
      (node (ref "TP139") (pin "1") (pinfunction "TP_1") (pintype "passive"))
      (node (ref "U22") (pin "39") (pinfunction "CDBUS1_39") (pintype "input"))
    )
    (net (code "36") (name "/UART_RX_FPGA1") (class "Default")
      (node (ref "TP142") (pin "1") (pinfunction "TP_1") (pintype "passive"))
      (node (ref "U22") (pin "52") (pinfunction "DDBUS1_52") (pintype "input"))
    )
    (net (code "37") (name "/UART_TX_FPGA0") (class "Default")
      (node (ref "TP137") (pin "1") (pinfunction "TP_1") (pintype "passive"))
      (node (ref "U22") (pin "38") (pinfunction "CDBUS0_38") (pintype "output"))
    )
    (net (code "38") (name "/UART_TX_FPGA1") (class "Default")
      (node (ref "TP141") (pin "1") (pinfunction "TP_1") (pintype "passive"))
      (node (ref "U22") (pin "48") (pinfunction "DDBUS0_48") (pintype "output"))
    )
    (net (code "39") (name "GND") (class "Default")
      (node (ref "C234") (pin "1") (pinfunction "1_1") (pintype "passive"))
      (node (ref "C235") (pin "1") (pinfunction "1_1") (pintype "passive"))
      (node (ref "C236") (pin "1") (pinfunction "1_1") (pintype "passive"))
      (node (ref "C237") (pin "1") (pinfunction "1_1") (pintype "passive"))
      (node (ref "C238") (pin "1") (pinfunction "1_1") (pintype "passive"))
      (node (ref "C239") (pin "1") (pinfunction "1_1") (pintype "passive"))
      (node (ref "C240") (pin "1") (pinfunction "1_1") (pintype "passive"))
      (node (ref "C241") (pin "1") (pinfunction "1_1") (pintype "passive"))
      (node (ref "C242") (pin "1") (pinfunction "1_1") (pintype "passive"))
      (node (ref "C243") (pin "1") (pinfunction "1_1") (pintype "passive"))
      (node (ref "C244") (pin "1") (pinfunction "1_1") (pintype "passive"))
      (node (ref "C245") (pin "1") (pinfunction "1_1") (pintype "passive"))
      (node (ref "C246") (pin "1") (pinfunction "1_1") (pintype "passive"))
      (node (ref "C247") (pin "1") (pinfunction "1_1") (pintype "passive"))
      (node (ref "C248") (pin "1") (pinfunction "1_1") (pintype "passive"))
      (node (ref "C249") (pin "1") (pinfunction "1_1") (pintype "passive"))
      (node (ref "C250") (pin "1") (pinfunction "1_1") (pintype "passive"))
      (node (ref "C251") (pin "1") (pinfunction "1_1") (pintype "passive"))
      (node (ref "C252") (pin "1") (pinfunction "1_1") (pintype "passive"))
      (node (ref "C253") (pin "1") (pinfunction "1_1") (pintype "passive"))
      (node (ref "DS10") (pin "2") (pinfunction "K_2") (pintype "passive"))
      (node (ref "DS11") (pin "2") (pinfunction "K_2") (pintype "passive"))
      (node (ref "DS12") (pin "2") (pinfunction "K_2") (pintype "passive"))
      (node (ref "DS32") (pin "2") (pinfunction "K_2") (pintype "passive"))
      (node (ref "DS33") (pin "2") (pinfunction "K_2") (pintype "passive"))
      (node (ref "DS5") (pin "2") (pinfunction "K_2") (pintype "passive"))
      (node (ref "DS6") (pin "2") (pinfunction "K_2") (pintype "passive"))
      (node (ref "DS7") (pin "2") (pinfunction "K_2") (pintype "passive"))
      (node (ref "DS8") (pin "2") (pinfunction "K_2") (pintype "passive"))
      (node (ref "DS9") (pin "2") (pinfunction "K_2") (pintype "passive"))
      (node (ref "J4") (pin "A1-B12") (pinfunction "GND_A1-B12") (pintype "power_in"))
      (node (ref "J4") (pin "B1-A12") (pinfunction "GND_B1-A12") (pintype "power_in"))
      (node (ref "P2") (pin "1") (pinfunction "1_1") (pintype "passive"))
      (node (ref "P2") (pin "11") (pinfunction "11_11") (pintype "passive"))
      (node (ref "P2") (pin "12") (pinfunction "12_12") (pintype "passive"))
      (node (ref "P2") (pin "13") (pinfunction "13_13") (pintype "passive"))
      (node (ref "P2") (pin "14") (pinfunction "14_14") (pintype "passive"))
      (node (ref "P2") (pin "3") (pinfunction "3_3") (pintype "passive"))
      (node (ref "P2") (pin "5") (pinfunction "5_5") (pintype "passive"))
      (node (ref "P2") (pin "7") (pinfunction "7_7") (pintype "passive"))
      (node (ref "P2") (pin "9") (pinfunction "9_9") (pintype "passive"))
      (node (ref "P3") (pin "1") (pinfunction "1_1") (pintype "passive"))
      (node (ref "P3") (pin "11") (pinfunction "11_11") (pintype "passive"))
      (node (ref "P3") (pin "12") (pinfunction "12_12") (pintype "passive"))
      (node (ref "P3") (pin "13") (pinfunction "13_13") (pintype "passive"))
      (node (ref "P3") (pin "14") (pinfunction "14_14") (pintype "passive"))
      (node (ref "P3") (pin "3") (pinfunction "3_3") (pintype "passive"))
      (node (ref "P3") (pin "5") (pinfunction "5_5") (pintype "passive"))
      (node (ref "P3") (pin "7") (pinfunction "7_7") (pintype "passive"))
      (node (ref "P3") (pin "9") (pinfunction "9_9") (pintype "passive"))
      (node (ref "P4") (pin "3") (pinfunction "3_3") (pintype "passive"))
      (node (ref "P5") (pin "3") (pinfunction "3_3") (pintype "passive"))
      (node (ref "R30") (pin "1") (pinfunction "1_1") (pintype "passive"))
      (node (ref "R83") (pin "2") (pinfunction "2_2") (pintype "passive"))
      (node (ref "R85") (pin "2") (pinfunction "2_2") (pintype "passive"))
      (node (ref "R93") (pin "1") (pinfunction "1_1") (pintype "passive"))
      (node (ref "U20") (pin "3") (pinfunction "GND_3") (pintype "power_in"))
      (node (ref "U21") (pin "15") (pinfunction "~{G}_15") (pintype "input"))
      (node (ref "U21") (pin "8") (pinfunction "GND_8") (pintype "power_in"))
      (node (ref "U22") (pin "1") (pinfunction "GND_1") (pintype "power_in"))
      (node (ref "U22") (pin "10") (pinfunction "AGND_10") (pintype "power_in"))
      (node (ref "U22") (pin "11") (pinfunction "GND_11") (pintype "power_in"))
      (node (ref "U22") (pin "13") (pinfunction "TEST_13") (pintype "input"))
      (node (ref "U22") (pin "15") (pinfunction "GND_15") (pintype "power_in"))
      (node (ref "U22") (pin "25") (pinfunction "GND_25") (pintype "power_in"))
      (node (ref "U22") (pin "35") (pinfunction "GND_35") (pintype "power_in"))
      (node (ref "U22") (pin "47") (pinfunction "GND_47") (pintype "power_in"))
      (node (ref "U22") (pin "5") (pinfunction "GND_5") (pintype "power_in"))
      (node (ref "U22") (pin "51") (pinfunction "GND_51") (pintype "power_in"))
      (node (ref "U22") (pin "65") (pinfunction "GND_65") (pintype "power_in"))
      (node (ref "U23") (pin "5") (pinfunction "VSS_5") (pintype "power_in"))
      (node (ref "U24") (pin "15") (pinfunction "~{G}_15") (pintype "input"))
      (node (ref "U24") (pin "8") (pinfunction "GND_8") (pintype "power_in"))
      (node (ref "U25") (pin "8") (pinfunction "GND_8") (pintype "power_in"))
      (node (ref "Y4") (pin "2") (pinfunction "GND_2") (pintype "power_in"))
      (node (ref "Y4") (pin "4") (pinfunction "GND_4") (pintype "power_in"))
    )
    (net (code "40") (name "Net-(DS5-A)") (class "Default")
      (node (ref "DS5") (pin "1") (pinfunction "A_1") (pintype "passive"))
      (node (ref "R94") (pin "1") (pinfunction "1_1") (pintype "passive"))
    )
    (net (code "41") (name "Net-(DS6-A)") (class "Default")
      (node (ref "DS6") (pin "1") (pinfunction "A_1") (pintype "passive"))
      (node (ref "R82") (pin "2") (pinfunction "2_2") (pintype "passive"))
    )
    (net (code "42") (name "Net-(DS7-A)") (class "Default")
      (node (ref "DS7") (pin "1") (pinfunction "A_1") (pintype "passive"))
      (node (ref "R96") (pin "1") (pinfunction "1_1") (pintype "passive"))
    )
    (net (code "43") (name "Net-(DS8-A)") (class "Default")
      (node (ref "DS8") (pin "1") (pinfunction "A_1") (pintype "passive"))
      (node (ref "R87") (pin "2") (pinfunction "2_2") (pintype "passive"))
    )
    (net (code "44") (name "Net-(DS9-A)") (class "Default")
      (node (ref "DS9") (pin "1") (pinfunction "A_1") (pintype "passive"))
      (node (ref "R98") (pin "1") (pinfunction "1_1") (pintype "passive"))
    )
    (net (code "45") (name "Net-(DS10-A)") (class "Default")
      (node (ref "DS10") (pin "1") (pinfunction "A_1") (pintype "passive"))
      (node (ref "R95") (pin "2") (pinfunction "2_2") (pintype "passive"))
    )
    (net (code "46") (name "Net-(DS11-A)") (class "Default")
      (node (ref "DS11") (pin "1") (pinfunction "A_1") (pintype "passive"))
      (node (ref "R101") (pin "1") (pinfunction "1_1") (pintype "passive"))
    )
    (net (code "47") (name "Net-(DS12-A)") (class "Default")
      (node (ref "DS12") (pin "1") (pinfunction "A_1") (pintype "passive"))
      (node (ref "R97") (pin "2") (pinfunction "2_2") (pintype "passive"))
    )
    (net (code "48") (name "Net-(DS31-K)") (class "Default")
      (node (ref "DS31") (pin "2") (pinfunction "K_2") (pintype "passive"))
      (node (ref "R30") (pin "2") (pinfunction "2_2") (pintype "passive"))
    )
    (net (code "49") (name "Net-(DS32-A)") (class "Default")
      (node (ref "DS32") (pin "1") (pinfunction "A_1") (pintype "passive"))
      (node (ref "R33") (pin "1") (pinfunction "1_1") (pintype "passive"))
    )
    (net (code "50") (name "Net-(DS33-A)") (class "Default")
      (node (ref "DS33") (pin "1") (pinfunction "A_1") (pintype "passive"))
      (node (ref "R53") (pin "1") (pinfunction "1_1") (pintype "passive"))
    )
    (net (code "51") (name "Net-(J4-CC1)") (class "Default")
      (node (ref "J4") (pin "A5") (pinfunction "CC1_A5") (pintype "bidirectional"))
      (node (ref "R85") (pin "1") (pinfunction "1_1") (pintype "passive"))
    )
    (net (code "52") (name "Net-(J4-CC2)") (class "Default")
      (node (ref "J4") (pin "B5") (pinfunction "CC2_B5") (pintype "bidirectional"))
      (node (ref "R83") (pin "1") (pinfunction "1_1") (pintype "passive"))
    )
    (net (code "53") (name "Net-(U21-~{A}{slash}B)") (class "Default")
      (node (ref "P4") (pin "2") (pinfunction "2_2") (pintype "passive"))
      (node (ref "R33") (pin "2") (pinfunction "2_2") (pintype "passive"))
      (node (ref "U21") (pin "1") (pinfunction "~{A}/B_1") (pintype "input"))
    )
    (net (code "54") (name "Net-(U22-REF)") (class "Default")
      (node (ref "R93") (pin "2") (pinfunction "2_2") (pintype "passive"))
      (node (ref "U22") (pin "6") (pinfunction "REF_6") (pintype "input"))
    )
    (net (code "55") (name "Net-(U22-RESET#)") (class "Default")
      (node (ref "R92") (pin "1") (pinfunction "1_1") (pintype "passive"))
      (node (ref "U22") (pin "14") (pinfunction "RESET#_14") (pintype "input"))
    )
    (net (code "56") (name "Net-(U22-VPHY)") (class "Default")
      (node (ref "C237") (pin "2") (pinfunction "2_2") (pintype "passive"))
      (node (ref "C238") (pin "2") (pinfunction "2_2") (pintype "passive"))
      (node (ref "L9") (pin "2") (pinfunction "2_2") (pintype "passive"))
      (node (ref "U22") (pin "4") (pinfunction "VPHY_4") (pintype "power_in"))
    )
    (net (code "57") (name "Net-(U22-VPLL)") (class "Default")
      (node (ref "C234") (pin "2") (pinfunction "2_2") (pintype "passive"))
      (node (ref "C235") (pin "2") (pinfunction "2_2") (pintype "passive"))
      (node (ref "L8") (pin "2") (pinfunction "2_2") (pintype "passive"))
      (node (ref "U22") (pin "9") (pinfunction "VPLL_9") (pintype "power_in"))
    )
    (net (code "58") (name "Net-(U23-DO)") (class "Default")
      (node (ref "R91") (pin "2") (pinfunction "2_2") (pintype "passive"))
      (node (ref "U23") (pin "4") (pinfunction "DO_4") (pintype "tri_state"))
    )
    (net (code "59") (name "Net-(U24-~{A}{slash}B)") (class "Default")
      (node (ref "P5") (pin "2") (pinfunction "2_2") (pintype "passive"))
      (node (ref "R53") (pin "2") (pinfunction "2_2") (pintype "passive"))
      (node (ref "U24") (pin "1") (pinfunction "~{A}/B_1") (pintype "input"))
    )
    (net (code "60") (name "Net-(U25-Q0)") (class "Default")
      (node (ref "R94") (pin "2") (pinfunction "2_2") (pintype "passive"))
      (node (ref "U25") (pin "15") (pinfunction "Q0_15") (pintype "output"))
    )
    (net (code "61") (name "Net-(U25-Q1)") (class "Default")
      (node (ref "R82") (pin "1") (pinfunction "1_1") (pintype "passive"))
      (node (ref "U25") (pin "1") (pinfunction "Q1_1") (pintype "output"))
    )
    (net (code "62") (name "Net-(U25-Q2)") (class "Default")
      (node (ref "R96") (pin "2") (pinfunction "2_2") (pintype "passive"))
      (node (ref "U25") (pin "2") (pinfunction "Q2_2") (pintype "output"))
    )
    (net (code "63") (name "Net-(U25-Q3)") (class "Default")
      (node (ref "R87") (pin "1") (pinfunction "1_1") (pintype "passive"))
      (node (ref "U25") (pin "3") (pinfunction "Q3_3") (pintype "output"))
    )
    (net (code "64") (name "Net-(U25-Q4)") (class "Default")
      (node (ref "R98") (pin "2") (pinfunction "2_2") (pintype "passive"))
      (node (ref "U25") (pin "4") (pinfunction "Q4_4") (pintype "output"))
    )
    (net (code "65") (name "Net-(U25-Q5)") (class "Default")
      (node (ref "R95") (pin "1") (pinfunction "1_1") (pintype "passive"))
      (node (ref "U25") (pin "5") (pinfunction "Q5_5") (pintype "output"))
    )
    (net (code "66") (name "Net-(U25-Q6)") (class "Default")
      (node (ref "R101") (pin "2") (pinfunction "2_2") (pintype "passive"))
      (node (ref "U25") (pin "6") (pinfunction "Q6_6") (pintype "output"))
    )
    (net (code "67") (name "Net-(U25-Q7)") (class "Default")
      (node (ref "R97") (pin "1") (pinfunction "1_1") (pintype "passive"))
      (node (ref "U25") (pin "7") (pinfunction "Q7_7") (pintype "output"))
    )
    (net (code "68") (name "unconnected-(J4-SBU1-PadA8)") (class "Default")
      (node (ref "J4") (pin "A8") (pinfunction "SBU1_A8") (pintype "bidirectional+no_connect"))
    )
    (net (code "69") (name "unconnected-(J4-SBU2-PadB8)") (class "Default")
      (node (ref "J4") (pin "B8") (pinfunction "SBU2_B8") (pintype "bidirectional+no_connect"))
    )
    (net (code "70") (name "unconnected-(U21-4A-Pad14)") (class "Default")
      (node (ref "U21") (pin "14") (pinfunction "4A_14") (pintype "input+no_connect"))
    )
    (net (code "71") (name "unconnected-(U21-4B-Pad13)") (class "Default")
      (node (ref "U21") (pin "13") (pinfunction "4B_13") (pintype "input+no_connect"))
    )
    (net (code "72") (name "unconnected-(U21-4Y-Pad12)") (class "Default")
      (node (ref "U21") (pin "12") (pinfunction "4Y_12") (pintype "output+no_connect"))
    )
    (net (code "73") (name "unconnected-(U22-ADBUS4-Pad21)") (class "Default")
      (node (ref "U22") (pin "21") (pinfunction "ADBUS4_21") (pintype "bidirectional+no_connect"))
    )
    (net (code "74") (name "unconnected-(U22-ADBUS5-Pad22)") (class "Default")
      (node (ref "U22") (pin "22") (pinfunction "ADBUS5_22") (pintype "bidirectional+no_connect"))
    )
    (net (code "75") (name "unconnected-(U22-ADBUS6-Pad23)") (class "Default")
      (node (ref "U22") (pin "23") (pinfunction "ADBUS6_23") (pintype "bidirectional+no_connect"))
    )
    (net (code "76") (name "unconnected-(U22-ADBUS7-Pad24)") (class "Default")
      (node (ref "U22") (pin "24") (pinfunction "ADBUS7_24") (pintype "bidirectional+no_connect"))
    )
    (net (code "77") (name "unconnected-(U22-BDBUS4-Pad30)") (class "Default")
      (node (ref "U22") (pin "30") (pinfunction "BDBUS4_30") (pintype "bidirectional+no_connect"))
    )
    (net (code "78") (name "unconnected-(U22-BDBUS5-Pad32)") (class "Default")
      (node (ref "U22") (pin "32") (pinfunction "BDBUS5_32") (pintype "bidirectional+no_connect"))
    )
    (net (code "79") (name "unconnected-(U22-BDBUS6-Pad33)") (class "Default")
      (node (ref "U22") (pin "33") (pinfunction "BDBUS6_33") (pintype "bidirectional+no_connect"))
    )
    (net (code "80") (name "unconnected-(U22-BDBUS7-Pad34)") (class "Default")
      (node (ref "U22") (pin "34") (pinfunction "BDBUS7_34") (pintype "bidirectional+no_connect"))
    )
    (net (code "81") (name "unconnected-(U22-CDBUS2-Pad40)") (class "Default")
      (node (ref "U22") (pin "40") (pinfunction "CDBUS2_40") (pintype "bidirectional+no_connect"))
    )
    (net (code "82") (name "unconnected-(U22-CDBUS3-Pad41)") (class "Default")
      (node (ref "U22") (pin "41") (pinfunction "CDBUS3_41") (pintype "bidirectional+no_connect"))
    )
    (net (code "83") (name "unconnected-(U22-CDBUS4-Pad43)") (class "Default")
      (node (ref "U22") (pin "43") (pinfunction "CDBUS4_43") (pintype "bidirectional+no_connect"))
    )
    (net (code "84") (name "unconnected-(U22-CDBUS5-Pad44)") (class "Default")
      (node (ref "U22") (pin "44") (pinfunction "CDBUS5_44") (pintype "bidirectional+no_connect"))
    )
    (net (code "85") (name "unconnected-(U22-CDBUS6-Pad45)") (class "Default")
      (node (ref "U22") (pin "45") (pinfunction "CDBUS6_45") (pintype "bidirectional+no_connect"))
    )
    (net (code "86") (name "unconnected-(U22-CDBUS7-Pad46)") (class "Default")
      (node (ref "U22") (pin "46") (pinfunction "CDBUS7_46") (pintype "bidirectional+no_connect"))
    )
    (net (code "87") (name "unconnected-(U22-DDBUS2-Pad53)") (class "Default")
      (node (ref "U22") (pin "53") (pinfunction "DDBUS2_53") (pintype "bidirectional+no_connect"))
    )
    (net (code "88") (name "unconnected-(U22-DDBUS3-Pad54)") (class "Default")
      (node (ref "U22") (pin "54") (pinfunction "DDBUS3_54") (pintype "bidirectional+no_connect"))
    )
    (net (code "89") (name "unconnected-(U22-DDBUS4-Pad55)") (class "Default")
      (node (ref "U22") (pin "55") (pinfunction "DDBUS4_55") (pintype "bidirectional+no_connect"))
    )
    (net (code "90") (name "unconnected-(U22-DDBUS5-Pad57)") (class "Default")
      (node (ref "U22") (pin "57") (pinfunction "DDBUS5_57") (pintype "bidirectional+no_connect"))
    )
    (net (code "91") (name "unconnected-(U22-DDBUS6-Pad58)") (class "Default")
      (node (ref "U22") (pin "58") (pinfunction "DDBUS6_58") (pintype "bidirectional+no_connect"))
    )
    (net (code "92") (name "unconnected-(U22-DDBUS7-Pad59)") (class "Default")
      (node (ref "U22") (pin "59") (pinfunction "DDBUS7_59") (pintype "bidirectional+no_connect"))
    )
    (net (code "93") (name "unconnected-(U22-SUSPEND#-Pad36)") (class "Default")
      (node (ref "U22") (pin "36") (pinfunction "SUSPEND#_36") (pintype "output+no_connect"))
    )
    (net (code "94") (name "unconnected-(U23-NC-Pad6)") (class "Default")
      (node (ref "U23") (pin "6") (pinfunction "NC_6") (pintype "passive+no_connect"))
    )
    (net (code "95") (name "unconnected-(U23-NC-Pad7)") (class "Default")
      (node (ref "U23") (pin "7") (pinfunction "NC_7") (pintype "passive+no_connect"))
    )
    (net (code "96") (name "unconnected-(U24-4A-Pad14)") (class "Default")
      (node (ref "U24") (pin "14") (pinfunction "4A_14") (pintype "input+no_connect"))
    )
    (net (code "97") (name "unconnected-(U24-4B-Pad13)") (class "Default")
      (node (ref "U24") (pin "13") (pinfunction "4B_13") (pintype "input+no_connect"))
    )
    (net (code "98") (name "unconnected-(U24-4Y-Pad12)") (class "Default")
      (node (ref "U24") (pin "12") (pinfunction "4Y_12") (pintype "output+no_connect"))
    )
    (net (code "99") (name "unconnected-(U25-Q7S-Pad9)") (class "Default")
      (node (ref "U25") (pin "9") (pinfunction "Q7S_9") (pintype "output+no_connect"))
    )
  )
)
